# SAM-M8Q_GPS_FeatherWing.net
KiCad netlist of a schematic drawn in EAGLE
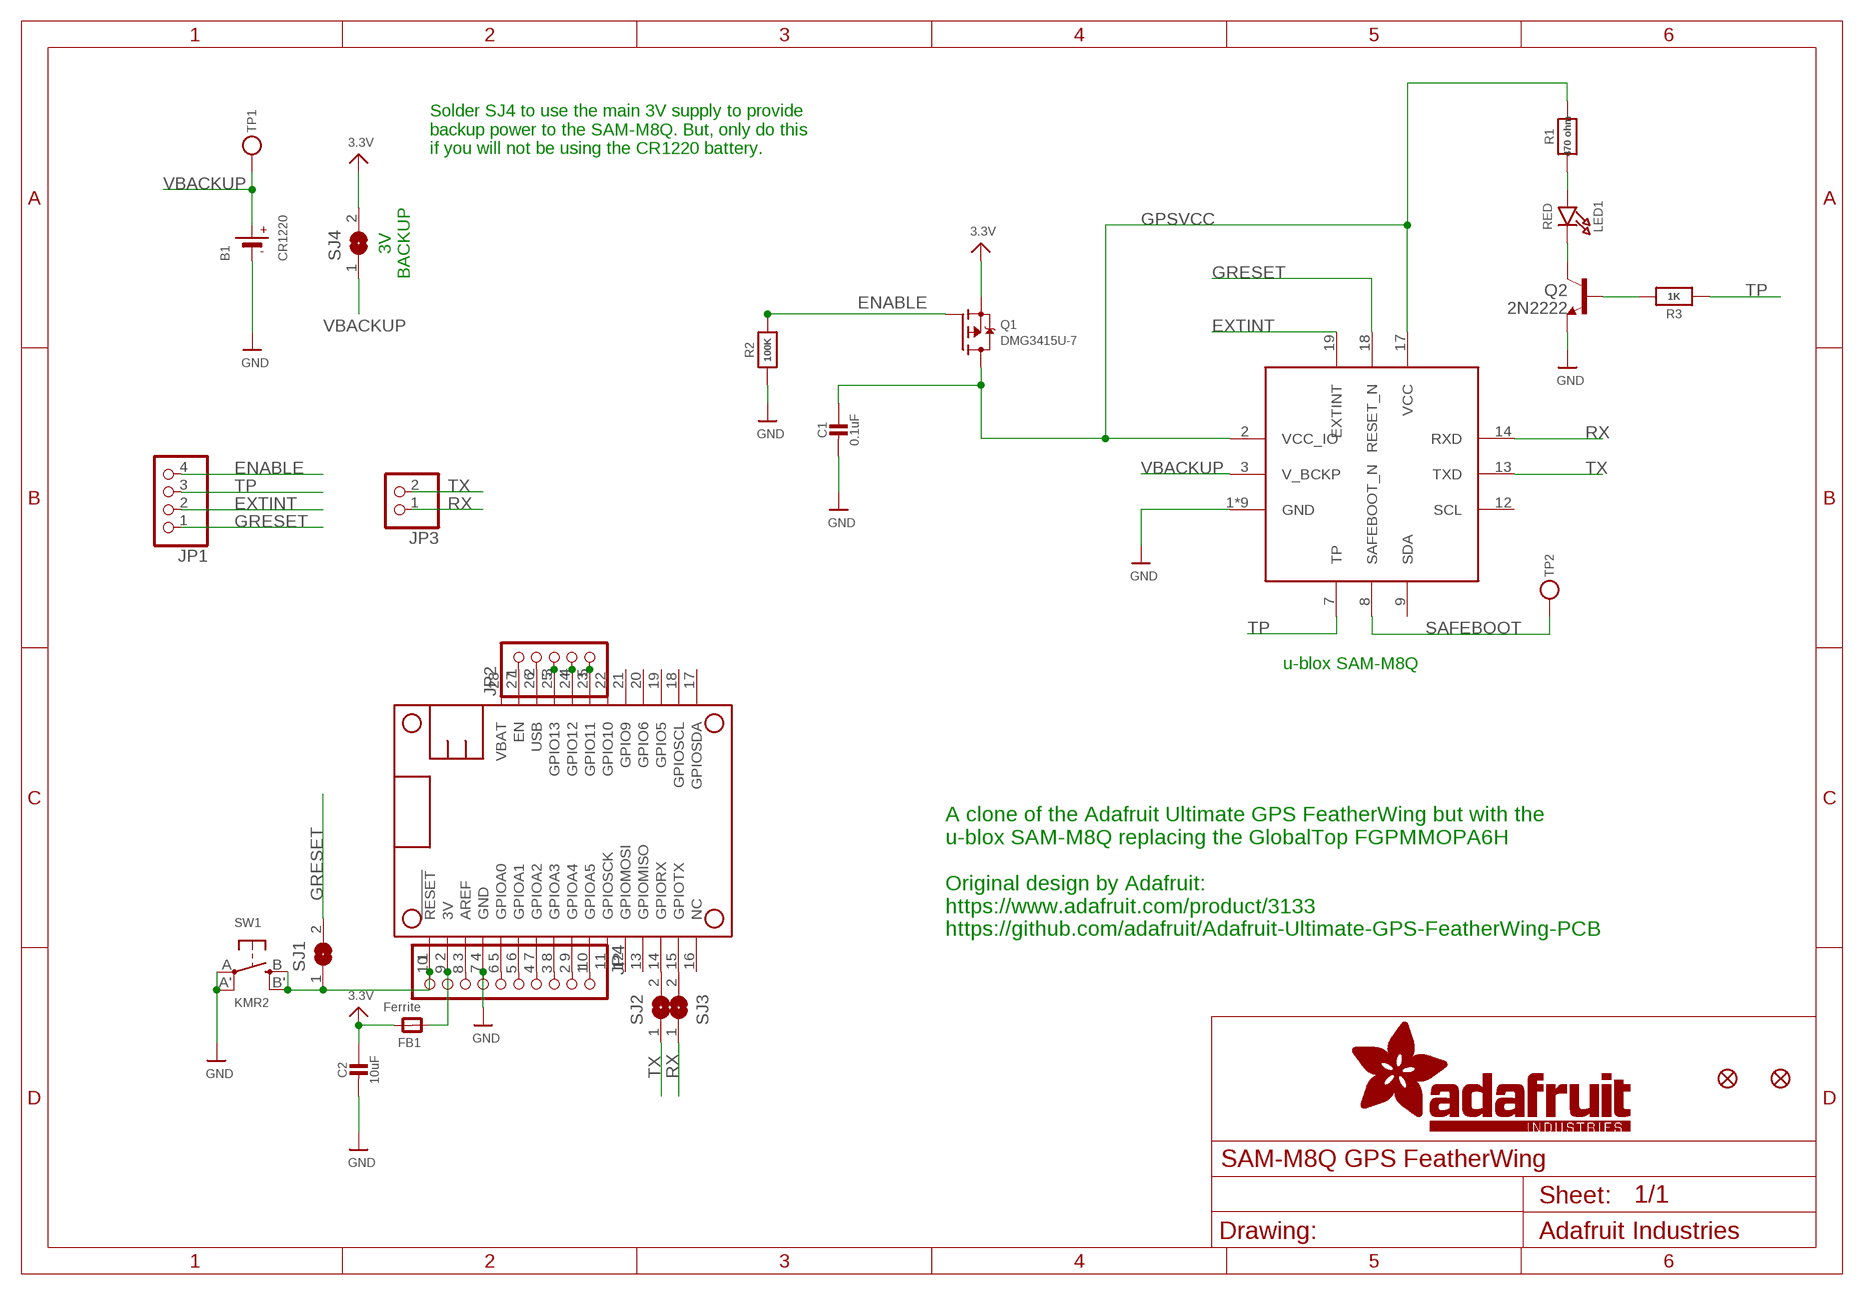
[diagram p0: schematic, sheet 1]

(export (version "E")
  (design (tool "Eeschema 10.0.6"))
  (components
    (comp (ref "B1")
      (value "CR1220")
      (footprint "eagle-import:CR1220-2")
      (libsource (lib "eagle-import") (part "BATTERYCR1220_2"))
    )
    (comp (ref "C1")
      (value "0.1uF")
      (footprint "eagle-import:0805-NO")
      (libsource (lib "eagle-import") (part "CAP_CERAMIC0805-NOOUTLINE"))
    )
    (comp (ref "C2")
      (value "10uF")
      (footprint "eagle-import:0805-NO")
      (libsource (lib "eagle-import") (part "CAP_CERAMIC0805-NOOUTLINE"))
    )
    (comp (ref "FB1")
      (value "Ferrite")
      (footprint "eagle-import:0805-NO")
      (libsource (lib "eagle-import") (part "FERRITE-0805NO"))
    )
    (comp (ref "FID1")
      (value "FIDUCIAL\"\"")
      (footprint "eagle-import:FIDUCIAL_1MM")
      (libsource (lib "eagle-import") (part "FIDUCIAL{dblquote}{dblquote}"))
    )
    (comp (ref "FID2")
      (value "FIDUCIAL\"\"")
      (footprint "eagle-import:FIDUCIAL_1MM")
      (libsource (lib "eagle-import") (part "FIDUCIAL{dblquote}{dblquote}"))
    )
    (comp (ref "JP1")
      (value "HEADER-1X4ROUND")
      (footprint "eagle-import:1X04_ROUND")
      (libsource (lib "eagle-import") (part "HEADER-1X4ROUND"))
    )
    (comp (ref "JP2")
      (value "HEADER-1X570MIL")
      (footprint "eagle-import:1X05_ROUND_70")
      (libsource (lib "eagle-import") (part "HEADER-1X570MIL"))
    )
    (comp (ref "JP3")
      (value "HEADER-1X2ROUND")
      (footprint "eagle-import:1X02_ROUND")
      (libsource (lib "eagle-import") (part "HEADER-1X2ROUND"))
    )
    (comp (ref "JP4")
      (value "HEADER-1X10ROUND")
      (footprint "eagle-import:1X10_ROUND")
      (libsource (lib "eagle-import") (part "HEADER-1X10ROUND"))
    )
    (comp (ref "LED1")
      (value "RED")
      (footprint "eagle-import:CHIPLED_0805_NOOUTLINE")
      (libsource (lib "eagle-import") (part "LED0805_NOOUTLINE"))
    )
    (comp (ref "MS1")
      (value "FEATHERWING")
      (footprint "eagle-import:FEATHERWING")
      (libsource (lib "eagle-import") (part "FEATHERWING"))
    )
    (comp (ref "Q1")
      (value "DMG3415U-7")
      (footprint "eagle-import:SOT23-WIDE")
      (libsource (lib "eagle-import") (part "MOSFET-PWIDE"))
    )
    (comp (ref "Q2")
      (value "2N2222")
      (footprint "eagle-import:SOT23-BEC")
      (libsource (lib "eagle-import") (part "-NPN-SOT23-BECMMBT2222ALT1"))
    )
    (comp (ref "R1")
      (value "470 ohm")
      (footprint "eagle-import:0805-NO")
      (libsource (lib "eagle-import") (part "RESISTOR0805_NOOUTLINE"))
    )
    (comp (ref "R2")
      (value "100K")
      (footprint "eagle-import:0805-NO")
      (libsource (lib "eagle-import") (part "RESISTOR0805_NOOUTLINE"))
    )
    (comp (ref "R3")
      (value "1K")
      (footprint "eagle-import:0805-NO")
      (libsource (lib "eagle-import") (part "RESISTOR0805_NOOUTLINE"))
    )
    (comp (ref "SJ1")
      (value "SOLDERJUMPER")
      (footprint "eagle-import:SOLDERJUMPER_ARROW_NOPASTE")
      (libsource (lib "eagle-import") (part "SOLDERJUMPER"))
    )
    (comp (ref "SJ2")
      (value "SOLDERJUMPERCLOSED")
      (footprint "eagle-import:SOLDERJUMPER_CLOSEDWIRE")
      (libsource (lib "eagle-import") (part "SOLDERJUMPERCLOSED"))
    )
    (comp (ref "SJ3")
      (value "SOLDERJUMPERCLOSED")
      (footprint "eagle-import:SOLDERJUMPER_CLOSEDWIRE")
      (libsource (lib "eagle-import") (part "SOLDERJUMPERCLOSED"))
    )
    (comp (ref "SJ4")
      (value "SOLDERJUMPER")
      (footprint "eagle-import:SOLDERJUMPER_ARROW_NOPASTE")
      (libsource (lib "eagle-import") (part "SOLDERJUMPER"))
    )
    (comp (ref "SW1")
      (value "KMR2")
      (footprint "eagle-import:BTN_KMR2_4.6X2.8")
      (libsource (lib "eagle-import") (part "SWITCH_TACT_SMT4.6X2.8"))
    )
    (comp (ref "TP1")
      (value "TESTPOINTROUND1.5MM")
      (footprint "eagle-import:TESTPOINT_ROUND_1.5MM")
      (libsource (lib "eagle-import") (part "TESTPOINTROUND1.5MM"))
    )
    (comp (ref "TP2")
      (value "TESTPOINTROUND1.5MM")
      (footprint "eagle-import:TESTPOINT_ROUND_1.5MM")
      (libsource (lib "eagle-import") (part "TESTPOINTROUND1.5MM"))
    )
    (comp (ref "U1")
      (value "SAM-M8Q")
      (footprint "eagle-import:SAM-M8Q")
      (libsource (lib "eagle-import") (part "SAM-M8Q"))
    )
  )
  (nets
    (net (code "1") (name "/ENABLE") (class "Default")
      (node (ref "JP1") (pin "4") (pinfunction "4_4") (pintype "passive"))
      (node (ref "Q1") (pin "1") (pinfunction "G_1") (pintype "passive"))
      (node (ref "R2") (pin "2") (pinfunction "2_2") (pintype "passive"))
    )
    (net (code "2") (name "/EXTINT") (class "Default")
      (node (ref "JP1") (pin "2") (pinfunction "2_2") (pintype "passive"))
      (node (ref "U1") (pin "19") (pinfunction "EXTINT_19") (pintype "bidirectional"))
    )
    (net (code "3") (name "/GPSVCC") (class "Default")
      (node (ref "C1") (pin "1") (pinfunction "1_1") (pintype "passive"))
      (node (ref "Q1") (pin "3") (pinfunction "D_3") (pintype "passive"))
      (node (ref "R1") (pin "2") (pinfunction "2_2") (pintype "passive"))
      (node (ref "U1") (pin "17") (pinfunction "VCC_17") (pintype "bidirectional"))
      (node (ref "U1") (pin "2") (pinfunction "VCC_IO_2") (pintype "bidirectional"))
    )
    (net (code "4") (name "/GRESET") (class "Default")
      (node (ref "JP1") (pin "1") (pinfunction "1_1") (pintype "passive"))
      (node (ref "SJ1") (pin "2") (pinfunction "2_2") (pintype "passive"))
      (node (ref "U1") (pin "18") (pinfunction "RESET_N_18") (pintype "bidirectional"))
    )
    (net (code "5") (name "/RX") (class "Default")
      (node (ref "JP3") (pin "1") (pinfunction "1_1") (pintype "passive"))
      (node (ref "SJ3") (pin "1") (pinfunction "1_1") (pintype "passive"))
      (node (ref "U1") (pin "14") (pinfunction "RXD_14") (pintype "bidirectional"))
    )
    (net (code "6") (name "/SAFEBOOT") (class "Default")
      (node (ref "TP2") (pin "P$1") (pinfunction "P$1_P$1") (pintype "bidirectional"))
      (node (ref "U1") (pin "8") (pinfunction "SAFEBOOT_N_8") (pintype "bidirectional"))
    )
    (net (code "7") (name "/TP") (class "Default")
      (node (ref "JP1") (pin "3") (pinfunction "3_3") (pintype "passive"))
      (node (ref "R3") (pin "1") (pinfunction "1_1") (pintype "passive"))
      (node (ref "U1") (pin "7") (pinfunction "TP_7") (pintype "bidirectional"))
    )
    (net (code "8") (name "/TX") (class "Default")
      (node (ref "JP3") (pin "2") (pinfunction "2_2") (pintype "passive"))
      (node (ref "SJ2") (pin "1") (pinfunction "1_1") (pintype "passive"))
      (node (ref "U1") (pin "13") (pinfunction "TXD_13") (pintype "bidirectional"))
    )
    (net (code "9") (name "/VBACKUP") (class "Default")
      (node (ref "B1") (pin "+") (pinfunction "+_+") (pintype "passive"))
      (node (ref "SJ4") (pin "1") (pinfunction "1_1") (pintype "passive"))
      (node (ref "TP1") (pin "P$1") (pinfunction "P$1_P$1") (pintype "bidirectional"))
      (node (ref "U1") (pin "3") (pinfunction "V_BCKP_3") (pintype "bidirectional"))
    )
    (net (code "10") (name "/VBAT") (class "Default")
      (node (ref "MS1") (pin "28") (pinfunction "VBAT_28") (pintype "power_in"))
    )
    (net (code "11") (name "3.3V") (class "Default")
      (node (ref "C2") (pin "1") (pinfunction "1_1") (pintype "passive"))
      (node (ref "FB1") (pin "2") (pinfunction "P$2_2") (pintype "passive"))
      (node (ref "Q1") (pin "2") (pinfunction "S_2") (pintype "passive"))
      (node (ref "SJ4") (pin "2") (pinfunction "2_2") (pintype "passive"))
    )
    (net (code "12") (name "GND") (class "Default")
      (node (ref "B1") (pin "-") (pinfunction "-_-") (pintype "passive"))
      (node (ref "C1") (pin "2") (pinfunction "2_2") (pintype "passive"))
      (node (ref "C2") (pin "2") (pinfunction "2_2") (pintype "passive"))
      (node (ref "JP4") (pin "7") (pinfunction "7_7") (pintype "passive"))
      (node (ref "MS1") (pin "4") (pinfunction "GND_4") (pintype "power_in"))
      (node (ref "Q2") (pin "E") (pinfunction "E_E") (pintype "passive"))
      (node (ref "R2") (pin "1") (pinfunction "1_1") (pintype "passive"))
      (node (ref "SW1") (pin "A") (pinfunction "P_A") (pintype "passive"))
      (node (ref "SW1") (pin "A'") (pinfunction "P1_A'") (pintype "passive"))
      (node (ref "U1") (pin "1") (pinfunction "GND_1") (pintype "bidirectional"))
      (node (ref "U1") (pin "10") (pinfunction "GND_10") (pintype "bidirectional"))
      (node (ref "U1") (pin "11") (pinfunction "GND_11") (pintype "bidirectional"))
      (node (ref "U1") (pin "15") (pinfunction "GND_15") (pintype "bidirectional"))
      (node (ref "U1") (pin "16") (pinfunction "GND_16") (pintype "bidirectional"))
      (node (ref "U1") (pin "20") (pinfunction "GND_20") (pintype "bidirectional"))
      (node (ref "U1") (pin "4") (pinfunction "GND_4") (pintype "bidirectional"))
      (node (ref "U1") (pin "5") (pinfunction "GND_5") (pintype "bidirectional"))
      (node (ref "U1") (pin "6") (pinfunction "GND_6") (pintype "bidirectional"))
    )
    (net (code "13") (name "Net-(FB1-P$1)") (class "Default")
      (node (ref "FB1") (pin "1") (pinfunction "P$1_1") (pintype "passive"))
      (node (ref "JP4") (pin "9") (pinfunction "9_9") (pintype "passive"))
      (node (ref "MS1") (pin "2") (pinfunction "3V_2") (pintype "power_in"))
    )
    (net (code "14") (name "Net-(LED1-PadA)") (class "Default")
      (node (ref "LED1") (pin "A") (pinfunction "A_A") (pintype "passive"))
      (node (ref "R1") (pin "1") (pinfunction "1_1") (pintype "passive"))
    )
    (net (code "15") (name "Net-(LED1-PadC)") (class "Default")
      (node (ref "LED1") (pin "C") (pinfunction "C_C") (pintype "passive"))
      (node (ref "Q2") (pin "C") (pinfunction "C_C") (pintype "passive"))
    )
    (net (code "16") (name "Net-(MS1-AREF)") (class "Default")
      (node (ref "JP4") (pin "8") (pinfunction "8_8") (pintype "passive"))
      (node (ref "MS1") (pin "3") (pinfunction "AREF_3") (pintype "passive"))
    )
    (net (code "17") (name "Net-(MS1-EN)") (class "Default")
      (node (ref "JP2") (pin "1") (pinfunction "1_1") (pintype "passive"))
      (node (ref "MS1") (pin "27") (pinfunction "EN_27") (pintype "passive"))
    )
    (net (code "18") (name "Net-(MS1-GPIO11)") (class "Default")
      (node (ref "JP2") (pin "5") (pinfunction "5_5") (pintype "passive"))
      (node (ref "MS1") (pin "23") (pinfunction "GPIO11_23") (pintype "bidirectional"))
    )
    (net (code "19") (name "Net-(MS1-GPIO12)") (class "Default")
      (node (ref "JP2") (pin "4") (pinfunction "4_4") (pintype "passive"))
      (node (ref "MS1") (pin "24") (pinfunction "GPIO12_24") (pintype "bidirectional"))
    )
    (net (code "20") (name "Net-(MS1-GPIO13)") (class "Default")
      (node (ref "JP2") (pin "3") (pinfunction "3_3") (pintype "passive"))
      (node (ref "MS1") (pin "25") (pinfunction "GPIO13_25") (pintype "bidirectional"))
    )
    (net (code "21") (name "Net-(MS1-GPIOA0)") (class "Default")
      (node (ref "JP4") (pin "6") (pinfunction "6_6") (pintype "passive"))
      (node (ref "MS1") (pin "5") (pinfunction "GPIOA0_5") (pintype "bidirectional"))
    )
    (net (code "22") (name "Net-(MS1-GPIOA1)") (class "Default")
      (node (ref "JP4") (pin "5") (pinfunction "5_5") (pintype "passive"))
      (node (ref "MS1") (pin "6") (pinfunction "GPIOA1_6") (pintype "bidirectional"))
    )
    (net (code "23") (name "Net-(MS1-GPIOA2)") (class "Default")
      (node (ref "JP4") (pin "4") (pinfunction "4_4") (pintype "passive"))
      (node (ref "MS1") (pin "7") (pinfunction "GPIOA2_7") (pintype "bidirectional"))
    )
    (net (code "24") (name "Net-(MS1-GPIOA3)") (class "Default")
      (node (ref "JP4") (pin "3") (pinfunction "3_3") (pintype "passive"))
      (node (ref "MS1") (pin "8") (pinfunction "GPIOA3_8") (pintype "bidirectional"))
    )
    (net (code "25") (name "Net-(MS1-GPIOA4)") (class "Default")
      (node (ref "JP4") (pin "2") (pinfunction "2_2") (pintype "passive"))
      (node (ref "MS1") (pin "9") (pinfunction "GPIOA4_9") (pintype "bidirectional"))
    )
    (net (code "26") (name "Net-(MS1-GPIOA5)") (class "Default")
      (node (ref "JP4") (pin "1") (pinfunction "1_1") (pintype "passive"))
      (node (ref "MS1") (pin "10") (pinfunction "GPIOA5_10") (pintype "bidirectional"))
    )
    (net (code "27") (name "Net-(MS1-GPIORX)") (class "Default")
      (node (ref "MS1") (pin "14") (pinfunction "GPIORX_14") (pintype "bidirectional"))
      (node (ref "SJ2") (pin "2") (pinfunction "2_2") (pintype "passive"))
    )
    (net (code "28") (name "Net-(MS1-GPIOTX)") (class "Default")
      (node (ref "MS1") (pin "15") (pinfunction "GPIOTX_15") (pintype "bidirectional"))
      (node (ref "SJ3") (pin "2") (pinfunction "2_2") (pintype "passive"))
    )
    (net (code "29") (name "Net-(MS1-USB)") (class "Default")
      (node (ref "JP2") (pin "2") (pinfunction "2_2") (pintype "passive"))
      (node (ref "MS1") (pin "26") (pinfunction "USB_26") (pintype "power_in"))
    )
    (net (code "30") (name "Net-(MS1-~{RESET})") (class "Default")
      (node (ref "JP4") (pin "10") (pinfunction "10_10") (pintype "passive"))
      (node (ref "MS1") (pin "1") (pinfunction "~{RESET}_1") (pintype "input"))
      (node (ref "SJ1") (pin "1") (pinfunction "1_1") (pintype "passive"))
      (node (ref "SW1") (pin "B") (pinfunction "S_B") (pintype "passive"))
      (node (ref "SW1") (pin "B'") (pinfunction "S1_B'") (pintype "passive"))
    )
    (net (code "31") (name "Net-(Q2-PadB)") (class "Default")
      (node (ref "Q2") (pin "B") (pinfunction "B_B") (pintype "passive"))
      (node (ref "R3") (pin "2") (pinfunction "2_2") (pintype "passive"))
    )
    (net (code "32") (name "unconnected-(MS1-GPIO5-Pad19)") (class "Default")
      (node (ref "MS1") (pin "19") (pinfunction "GPIO5_19") (pintype "bidirectional"))
    )
    (net (code "33") (name "unconnected-(MS1-GPIO6-Pad20)") (class "Default")
      (node (ref "MS1") (pin "20") (pinfunction "GPIO6_20") (pintype "bidirectional"))
    )
    (net (code "34") (name "unconnected-(MS1-GPIO9-Pad21)") (class "Default")
      (node (ref "MS1") (pin "21") (pinfunction "GPIO9_21") (pintype "bidirectional"))
    )
    (net (code "35") (name "unconnected-(MS1-GPIO10-Pad22)") (class "Default")
      (node (ref "MS1") (pin "22") (pinfunction "GPIO10_22") (pintype "bidirectional"))
    )
    (net (code "36") (name "unconnected-(MS1-GPIOMISO-Pad13)") (class "Default")
      (node (ref "MS1") (pin "13") (pinfunction "GPIOMISO_13") (pintype "bidirectional"))
    )
    (net (code "37") (name "unconnected-(MS1-GPIOMOSI-Pad12)") (class "Default")
      (node (ref "MS1") (pin "12") (pinfunction "GPIOMOSI_12") (pintype "bidirectional"))
    )
    (net (code "38") (name "unconnected-(MS1-GPIOSCK-Pad11)") (class "Default")
      (node (ref "MS1") (pin "11") (pinfunction "GPIOSCK_11") (pintype "bidirectional"))
    )
    (net (code "39") (name "unconnected-(MS1-GPIOSCL-Pad18)") (class "Default")
      (node (ref "MS1") (pin "18") (pinfunction "GPIOSCL_18") (pintype "bidirectional"))
    )
    (net (code "40") (name "unconnected-(MS1-GPIOSDA-Pad17)") (class "Default")
      (node (ref "MS1") (pin "17") (pinfunction "GPIOSDA_17") (pintype "bidirectional"))
    )
    (net (code "41") (name "unconnected-(MS1-NC-Pad16)") (class "Default")
      (node (ref "MS1") (pin "16") (pinfunction "NC_16") (pintype "passive"))
    )
    (net (code "42") (name "unconnected-(U1-SCL-Pad12)") (class "Default")
      (node (ref "U1") (pin "12") (pinfunction "SCL_12") (pintype "bidirectional"))
    )
    (net (code "43") (name "unconnected-(U1-SDA-Pad9)") (class "Default")
      (node (ref "U1") (pin "9") (pinfunction "SDA_9") (pintype "bidirectional"))
    )
  )
)
